# V0p2_Main_PCB2.net
KiCad netlist of a schematic drawn in EAGLE
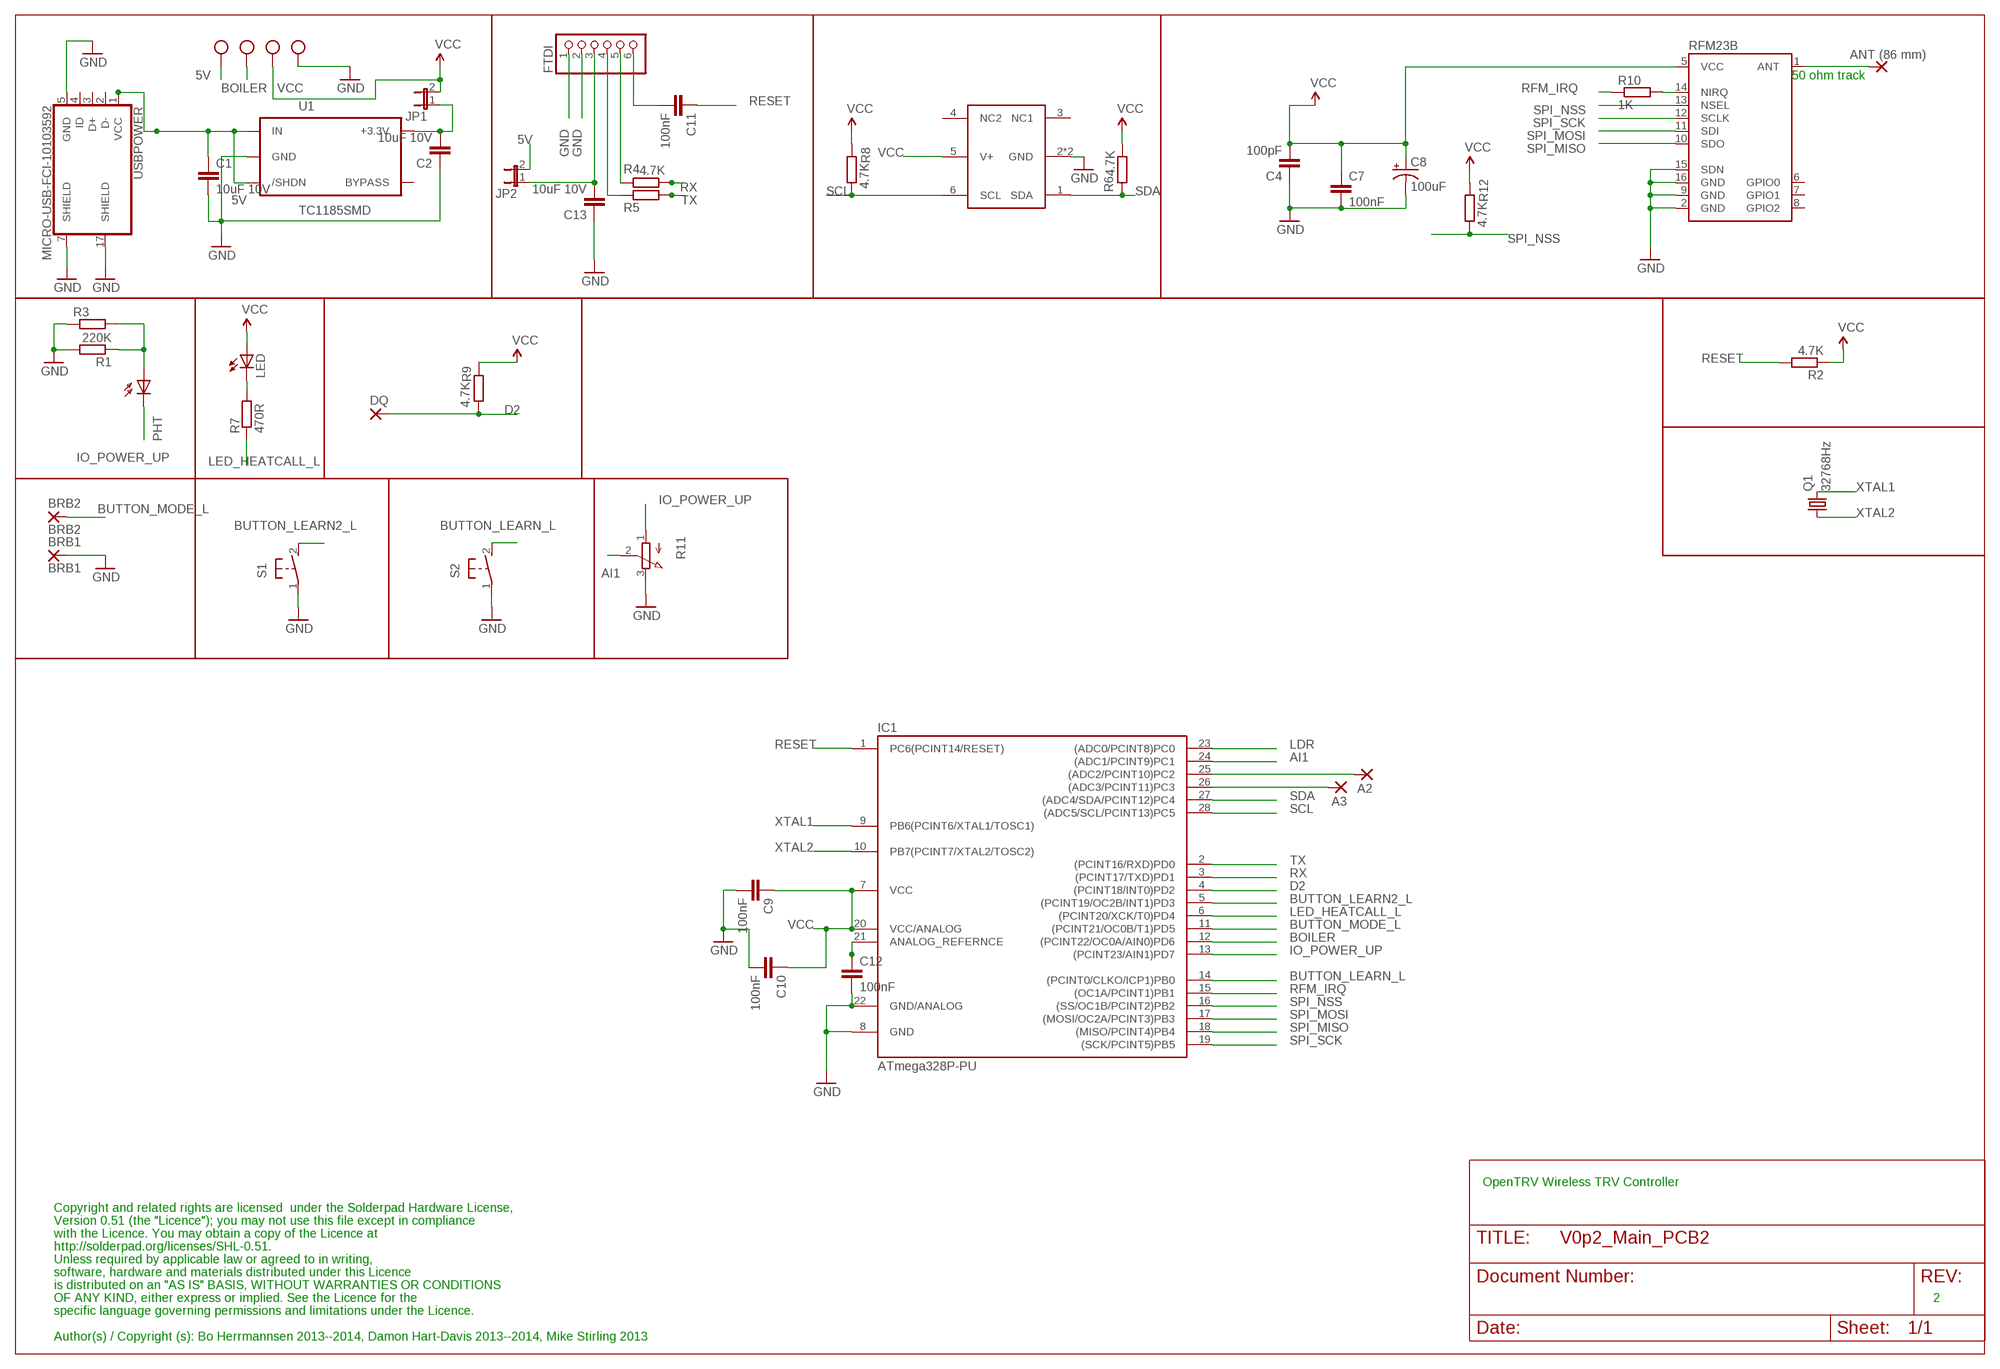
[diagram p0: schematic, sheet 1]

(export (version "E")
  (design (tool "Eeschema 10.0.6"))
  (components
    (comp (ref "A2")
      (value "2,15/1,0")
      (footprint "eagle-import:2,15_1,0")
      (libsource (lib "eagle-import") (part "2,15/1,0"))
    )
    (comp (ref "A3")
      (value "2,15/1,0")
      (footprint "eagle-import:2,15_1,0")
      (libsource (lib "eagle-import") (part "2,15/1,0"))
    )
    (comp (ref "ANT1")
      (value "ANT (86 mm)")
      (footprint "eagle-import:2,15_1,0")
      (libsource (lib "eagle-import") (part "2,15/1,0"))
    )
    (comp (ref "BRB1")
      (value "BRB1")
      (footprint "eagle-import:2,15_1,0")
      (libsource (lib "eagle-import") (part "2,15/1,0"))
    )
    (comp (ref "BRB2")
      (value "BRB2")
      (footprint "eagle-import:2,15_1,0")
      (libsource (lib "eagle-import") (part "2,15/1,0"))
    )
    (comp (ref "C1")
      (value "10uF 10V")
      (footprint "eagle-import:C0603")
      (libsource (lib "eagle-import") (part "C-EUC0603"))
    )
    (comp (ref "C2")
      (value "10uF 10V")
      (footprint "eagle-import:C0603")
      (libsource (lib "eagle-import") (part "C-EUC0603"))
    )
    (comp (ref "C4")
      (value "100pF")
      (footprint "eagle-import:C0603")
      (libsource (lib "eagle-import") (part "C-EUC0603"))
    )
    (comp (ref "C7")
      (value "100nF")
      (footprint "eagle-import:C0603")
      (libsource (lib "eagle-import") (part "C-EUC0603"))
    )
    (comp (ref "C8")
      (value "100uF")
      (footprint "eagle-import:EIA3216")
      (libsource (lib "eagle-import") (part "CAP_POL1206"))
    )
    (comp (ref "C9")
      (value "100nF")
      (footprint "eagle-import:C0603")
      (libsource (lib "eagle-import") (part "C-EUC0603"))
    )
    (comp (ref "C10")
      (value "100nF")
      (footprint "eagle-import:C0603")
      (libsource (lib "eagle-import") (part "C-EUC0603"))
    )
    (comp (ref "C11")
      (value "100nF")
      (footprint "eagle-import:C0603")
      (libsource (lib "eagle-import") (part "C-EUC0603"))
    )
    (comp (ref "C12")
      (value "100nF")
      (footprint "eagle-import:C0603")
      (libsource (lib "eagle-import") (part "C-EUC0603"))
    )
    (comp (ref "C13")
      (value "10uF 10V")
      (footprint "eagle-import:C0603")
      (libsource (lib "eagle-import") (part "C-EUC0603"))
    )
    (comp (ref "DQ")
      (value "2,15/1,0")
      (footprint "eagle-import:2,15_1,0")
      (libsource (lib "eagle-import") (part "2,15/1,0"))
    )
    (comp (ref "FTDI")
      (value "PINHD-1X6/90")
      (footprint "eagle-import:1X06_90")
      (libsource (lib "eagle-import") (part "PINHD-1X6/90"))
    )
    (comp (ref "IC1")
      (value "ATmega328P-PU")
      (footprint "eagle-import:DIL28-3")
      (libsource (lib "eagle-import") (part "ATMEGA168-PU"))
    )
    (comp (ref "JP1")
      (value "JP1E")
      (footprint "eagle-import:JP1")
      (libsource (lib "eagle-import") (part "JP1E"))
    )
    (comp (ref "JP2")
      (value "JP1E")
      (footprint "eagle-import:JP1")
      (libsource (lib "eagle-import") (part "JP1E"))
    )
    (comp (ref "LED")
      (value "LED3MM")
      (footprint "eagle-import:LED3MM")
      (libsource (lib "eagle-import") (part "LED3MM"))
    )
    (comp (ref "PHT")
      (value "BPX65")
      (footprint "eagle-import:BPX65")
      (fields (field (name "MPN") "BPX65."))
      (libsource (lib "eagle-import") (part "BPX65"))
    )
    (comp (ref "Q1")
      (value "32768Hz")
      (footprint "eagle-import:MC-306")
      (fields (field (name "MPN") "MC-306 60.0KHZ  100PPM ,12.5PF"))
      (libsource (lib "eagle-import") (part "MC-306"))
    )
    (comp (ref "R1")
      (value "220K")
      (footprint "eagle-import:R0603")
      (libsource (lib "eagle-import") (part "R-EU_R0603"))
    )
    (comp (ref "R2")
      (value "4.7K")
      (footprint "eagle-import:R0603")
      (libsource (lib "eagle-import") (part "R-EU_R0603"))
    )
    (comp (ref "R3")
      (value "R-EU_0309/V")
      (footprint "eagle-import:0309V")
      (libsource (lib "eagle-import") (part "R-EU_0309/V"))
    )
    (comp (ref "R4")
      (value "4.7K")
      (footprint "eagle-import:R0603")
      (libsource (lib "eagle-import") (part "R-EU_R0603"))
    )
    (comp (ref "R5")
      (value "4.7K")
      (footprint "eagle-import:R0603")
      (libsource (lib "eagle-import") (part "R-EU_R0603"))
    )
    (comp (ref "R6")
      (value "4.7K")
      (footprint "eagle-import:R0603")
      (libsource (lib "eagle-import") (part "R-EU_R0603"))
    )
    (comp (ref "R7")
      (value "470R")
      (footprint "eagle-import:R0603")
      (libsource (lib "eagle-import") (part "R-EU_R0603"))
    )
    (comp (ref "R8")
      (value "4.7K")
      (footprint "eagle-import:R0603")
      (libsource (lib "eagle-import") (part "R-EU_R0603"))
    )
    (comp (ref "R9")
      (value "4.7K")
      (footprint "eagle-import:R0603")
      (libsource (lib "eagle-import") (part "R-EU_R0603"))
    )
    (comp (ref "R10")
      (value "1K")
      (footprint "eagle-import:R0603")
      (libsource (lib "eagle-import") (part "R-EU_R0603"))
    )
    (comp (ref "R11")
      (value "EVUE2A")
      (footprint "eagle-import:EVUE")
      (libsource (lib "eagle-import") (part "EVUE2A"))
    )
    (comp (ref "R12")
      (value "4.7K")
      (footprint "eagle-import:R0603")
      (libsource (lib "eagle-import") (part "R-EU_R0603"))
    )
    (comp (ref "RFM23B")
      (value "RFM23B")
      (footprint "eagle-import:RFM23-XXX-S1")
      (libsource (lib "eagle-import") (part "RFM23B"))
    )
    (comp (ref "S1")
      (value "31-XX")
      (footprint "eagle-import:B3F-31XX")
      (libsource (lib "eagle-import") (part "31-XX"))
    )
    (comp (ref "S2")
      (value "31-XX")
      (footprint "eagle-import:B3F-31XX")
      (libsource (lib "eagle-import") (part "31-XX"))
    )
    (comp (ref "U$4")
      (value "SHT21")
      (footprint "eagle-import:SHT21")
      (libsource (lib "eagle-import") (part "SHT21"))
    )
    (comp (ref "U1")
      (value "TC1185SMD")
      (footprint "eagle-import:TC1185")
      (libsource (lib "eagle-import") (part "TC1185SMD"))
    )
    (comp (ref "USBPOWER")
      (value "MICRO-USB-FCI-10103592")
      (footprint "eagle-import:MICRO-USB-FCI-10103592")
      (libsource (lib "eagle-import") (part "MICRO-USB-FCI-10103592"))
    )
    (comp (ref "X1")
      (value "W237-102")
      (footprint "eagle-import:SCREWTERMINAL")
      (fields (field (name "MPN") "237-102"))
      (libsource (lib "eagle-import") (part "W237-102"))
    )
    (comp (ref "X2")
      (value "W237-102")
      (footprint "eagle-import:SCREWTERMINAL")
      (fields (field (name "MPN") "237-102"))
      (libsource (lib "eagle-import") (part "W237-102"))
    )
  )
  (nets
    (net (code "1") (name "/5V") (class "Default")
      (node (ref "C1") (pin "1") (pinfunction "1_1") (pintype "passive"))
      (node (ref "JP2") (pin "2") (pinfunction "2_2") (pintype "passive"))
      (node (ref "U1") (pin "1") (pinfunction "IN_1") (pintype "passive"))
      (node (ref "U1") (pin "3") (pinfunction "/SHDN_3") (pintype "passive"))
      (node (ref "USBPOWER") (pin "1") (pinfunction "VCC_1") (pintype "bidirectional"))
      (node (ref "X1") (pin "2") (pinfunction "KL_2") (pintype "passive"))
    )
    (net (code "2") (name "/AI1") (class "Default")
      (node (ref "IC1") (pin "24") (pinfunction "(ADC1/PCINT9)PC1_24") (pintype "bidirectional"))
      (node (ref "R11") (pin "2") (pinfunction "S_2") (pintype "passive"))
    )
    (net (code "3") (name "/BOILER") (class "Default")
      (node (ref "IC1") (pin "12") (pinfunction "(PCINT22/OC0A/AIN0)PD6_12") (pintype "bidirectional"))
      (node (ref "X1") (pin "1") (pinfunction "KL_1") (pintype "passive"))
    )
    (net (code "4") (name "/BUTTON_LEARN2_L") (class "Default")
      (node (ref "IC1") (pin "5") (pinfunction "(PCINT19/OC2B/INT1)PD3_5") (pintype "bidirectional"))
      (node (ref "S1") (pin "2") (pinfunction "S_2") (pintype "passive"))
    )
    (net (code "5") (name "/BUTTON_LEARN_L") (class "Default")
      (node (ref "IC1") (pin "14") (pinfunction "(PCINT0/CLKO/ICP1)PB0_14") (pintype "bidirectional"))
      (node (ref "S2") (pin "2") (pinfunction "S_2") (pintype "passive"))
    )
    (net (code "6") (name "/BUTTON_MODE_L") (class "Default")
      (node (ref "BRB2") (pin "1") (pinfunction "P_1") (pintype "passive"))
      (node (ref "IC1") (pin "11") (pinfunction "(PCINT21/OC0B/T1)PD5_11") (pintype "bidirectional"))
    )
    (net (code "7") (name "/D2") (class "Default")
      (node (ref "DQ") (pin "1") (pinfunction "P_1") (pintype "passive"))
      (node (ref "IC1") (pin "4") (pinfunction "(PCINT18/INT0)PD2_4") (pintype "bidirectional"))
      (node (ref "R9") (pin "1") (pinfunction "1_1") (pintype "passive"))
    )
    (net (code "8") (name "/IO_POWER_UP") (class "Default")
      (node (ref "IC1") (pin "13") (pinfunction "(PCINT23/AIN1)PD7_13") (pintype "bidirectional"))
      (node (ref "PHT") (pin "K") (pinfunction "C_K") (pintype "passive"))
      (node (ref "R11") (pin "1") (pinfunction "A_1") (pintype "passive"))
    )
    (net (code "9") (name "/LDR") (class "Default")
      (node (ref "IC1") (pin "23") (pinfunction "(ADC0/PCINT8)PC0_23") (pintype "bidirectional"))
      (node (ref "PHT") (pin "A") (pinfunction "A_A") (pintype "passive"))
      (node (ref "R1") (pin "1") (pinfunction "1_1") (pintype "passive"))
      (node (ref "R3") (pin "2") (pinfunction "2_2") (pintype "passive"))
    )
    (net (code "10") (name "/LED_HEATCALL_L") (class "Default")
      (node (ref "IC1") (pin "6") (pinfunction "(PCINT20/XCK/T0)PD4_6") (pintype "bidirectional"))
      (node (ref "R7") (pin "1") (pinfunction "1_1") (pintype "passive"))
    )
    (net (code "11") (name "/RESET") (class "Default")
      (node (ref "C11") (pin "1") (pinfunction "1_1") (pintype "passive"))
      (node (ref "IC1") (pin "1") (pinfunction "PC6(PCINT14/RESET)_1") (pintype "bidirectional"))
      (node (ref "R2") (pin "2") (pinfunction "2_2") (pintype "passive"))
    )
    (net (code "12") (name "/RFM_IRQ") (class "Default")
      (node (ref "IC1") (pin "15") (pinfunction "(OC1A/PCINT1)PB1_15") (pintype "bidirectional"))
      (node (ref "R10") (pin "1") (pinfunction "1_1") (pintype "passive"))
    )
    (net (code "13") (name "/RX") (class "Default")
      (node (ref "IC1") (pin "3") (pinfunction "(PCINT17/TXD)PD1_3") (pintype "bidirectional"))
      (node (ref "R4") (pin "1") (pinfunction "1_1") (pintype "passive"))
    )
    (net (code "14") (name "/SCL") (class "Default")
      (node (ref "IC1") (pin "28") (pinfunction "(ADC5/SCL/PCINT13)PC5_28") (pintype "bidirectional"))
      (node (ref "R8") (pin "1") (pinfunction "1_1") (pintype "passive"))
      (node (ref "U$4") (pin "6") (pinfunction "SCL_6") (pintype "bidirectional"))
    )
    (net (code "15") (name "/SDA") (class "Default")
      (node (ref "IC1") (pin "27") (pinfunction "(ADC4/SDA/PCINT12)PC4_27") (pintype "bidirectional"))
      (node (ref "R6") (pin "2") (pinfunction "2_2") (pintype "passive"))
      (node (ref "U$4") (pin "1") (pinfunction "SDA_1") (pintype "bidirectional"))
    )
    (net (code "16") (name "/SPI_MISO") (class "Default")
      (node (ref "IC1") (pin "18") (pinfunction "(MISO/PCINT4)PB4_18") (pintype "bidirectional"))
      (node (ref "RFM23B") (pin "10") (pinfunction "SDO_10") (pintype "output"))
    )
    (net (code "17") (name "/SPI_MOSI") (class "Default")
      (node (ref "IC1") (pin "17") (pinfunction "(MOSI/OC2A/PCINT3)PB3_17") (pintype "bidirectional"))
      (node (ref "RFM23B") (pin "11") (pinfunction "SDI_11") (pintype "input"))
    )
    (net (code "18") (name "/SPI_NSS") (class "Default")
      (node (ref "IC1") (pin "16") (pinfunction "(SS/OC1B/PCINT2)PB2_16") (pintype "bidirectional"))
      (node (ref "R12") (pin "1") (pinfunction "1_1") (pintype "passive"))
      (node (ref "RFM23B") (pin "13") (pinfunction "NSEL_13") (pintype "input"))
    )
    (net (code "19") (name "/SPI_SCK") (class "Default")
      (node (ref "IC1") (pin "19") (pinfunction "(SCK/PCINT5)PB5_19") (pintype "bidirectional"))
      (node (ref "RFM23B") (pin "12") (pinfunction "SCLK_12") (pintype "input"))
    )
    (net (code "20") (name "/TX") (class "Default")
      (node (ref "IC1") (pin "2") (pinfunction "(PCINT16/RXD)PD0_2") (pintype "bidirectional"))
      (node (ref "R5") (pin "1") (pinfunction "1_1") (pintype "passive"))
    )
    (net (code "21") (name "/XTAL1") (class "Default")
      (node (ref "IC1") (pin "9") (pinfunction "PB6(PCINT6/XTAL1/TOSC1)_9") (pintype "bidirectional"))
      (node (ref "Q1") (pin "4") (pinfunction "2_4") (pintype "passive"))
    )
    (net (code "22") (name "/XTAL2") (class "Default")
      (node (ref "IC1") (pin "10") (pinfunction "PB7(PCINT7/XTAL2/TOSC2)_10") (pintype "bidirectional"))
      (node (ref "Q1") (pin "1") (pinfunction "1_1") (pintype "passive"))
    )
    (net (code "23") (name "GND") (class "Default")
      (node (ref "BRB1") (pin "1") (pinfunction "P_1") (pintype "passive"))
      (node (ref "C1") (pin "2") (pinfunction "2_2") (pintype "passive"))
      (node (ref "C10") (pin "2") (pinfunction "2_2") (pintype "passive"))
      (node (ref "C12") (pin "2") (pinfunction "2_2") (pintype "passive"))
      (node (ref "C13") (pin "1") (pinfunction "1_1") (pintype "passive"))
      (node (ref "C2") (pin "1") (pinfunction "1_1") (pintype "passive"))
      (node (ref "C4") (pin "1") (pinfunction "1_1") (pintype "passive"))
      (node (ref "C7") (pin "2") (pinfunction "2_2") (pintype "passive"))
      (node (ref "C8") (pin "C") (pinfunction "-_C") (pintype "passive"))
      (node (ref "C9") (pin "2") (pinfunction "2_2") (pintype "passive"))
      (node (ref "FTDI") (pin "1") (pinfunction "1_1") (pintype "passive"))
      (node (ref "FTDI") (pin "2") (pinfunction "2_2") (pintype "passive"))
      (node (ref "IC1") (pin "22") (pinfunction "GND/ANALOG_22") (pintype "power_in"))
      (node (ref "IC1") (pin "8") (pinfunction "GND_8") (pintype "power_in"))
      (node (ref "R1") (pin "2") (pinfunction "2_2") (pintype "passive"))
      (node (ref "R11") (pin "3") (pinfunction "E_3") (pintype "passive"))
      (node (ref "R3") (pin "1") (pinfunction "1_1") (pintype "passive"))
      (node (ref "RFM23B") (pin "15") (pinfunction "SDN_15") (pintype "input"))
      (node (ref "RFM23B") (pin "16") (pinfunction "GND_16") (pintype "power_in"))
      (node (ref "RFM23B") (pin "2") (pinfunction "GND_2") (pintype "power_in"))
      (node (ref "RFM23B") (pin "9") (pinfunction "GND_9") (pintype "power_in"))
      (node (ref "S1") (pin "1") (pinfunction "P_1") (pintype "passive"))
      (node (ref "S2") (pin "1") (pinfunction "P_1") (pintype "passive"))
      (node (ref "U$4") (pin "2") (pinfunction "GND_2") (pintype "bidirectional"))
      (node (ref "U$4") (pin "P$1") (pinfunction "GND_P$1") (pintype "bidirectional"))
      (node (ref "U1") (pin "2") (pinfunction "GND_2") (pintype "passive"))
      (node (ref "USBPOWER") (pin "17") (pinfunction "SHIELD_17") (pintype "bidirectional"))
      (node (ref "USBPOWER") (pin "5") (pinfunction "GND_5") (pintype "bidirectional"))
      (node (ref "USBPOWER") (pin "7") (pinfunction "SHIELD_7") (pintype "bidirectional"))
      (node (ref "X2") (pin "2") (pinfunction "KL_2") (pintype "passive"))
    )
    (net (code "24") (name "Net-(A2-P)") (class "Default")
      (node (ref "A2") (pin "1") (pinfunction "P_1") (pintype "passive"))
      (node (ref "IC1") (pin "25") (pinfunction "(ADC2/PCINT10)PC2_25") (pintype "bidirectional"))
    )
    (net (code "25") (name "Net-(A3-P)") (class "Default")
      (node (ref "A3") (pin "1") (pinfunction "P_1") (pintype "passive"))
      (node (ref "IC1") (pin "26") (pinfunction "(ADC3/PCINT11)PC3_26") (pintype "bidirectional"))
    )
    (net (code "26") (name "Net-(ANT1-P)") (class "Default")
      (node (ref "ANT1") (pin "1") (pinfunction "P_1") (pintype "passive"))
      (node (ref "RFM23B") (pin "1") (pinfunction "ANT_1") (pintype "bidirectional"))
    )
    (net (code "27") (name "Net-(C11-Pad2)") (class "Default")
      (node (ref "C11") (pin "2") (pinfunction "2_2") (pintype "passive"))
      (node (ref "FTDI") (pin "6") (pinfunction "6_6") (pintype "passive"))
    )
    (net (code "28") (name "Net-(C13-Pad2)") (class "Default")
      (node (ref "C13") (pin "2") (pinfunction "2_2") (pintype "passive"))
      (node (ref "FTDI") (pin "3") (pinfunction "3_3") (pintype "passive"))
      (node (ref "JP2") (pin "1") (pinfunction "1_1") (pintype "passive"))
    )
    (net (code "29") (name "Net-(FTDI-Pad4)") (class "Default")
      (node (ref "FTDI") (pin "4") (pinfunction "4_4") (pintype "passive"))
      (node (ref "R5") (pin "2") (pinfunction "2_2") (pintype "passive"))
    )
    (net (code "30") (name "Net-(FTDI-Pad5)") (class "Default")
      (node (ref "FTDI") (pin "5") (pinfunction "5_5") (pintype "passive"))
      (node (ref "R4") (pin "2") (pinfunction "2_2") (pintype "passive"))
    )
    (net (code "31") (name "Net-(IC1-ANALOG_REFERNCE)") (class "Default")
      (node (ref "C12") (pin "1") (pinfunction "1_1") (pintype "passive"))
      (node (ref "IC1") (pin "21") (pinfunction "ANALOG_REFERNCE_21") (pintype "passive"))
    )
    (net (code "32") (name "Net-(LED-C)") (class "Default")
      (node (ref "LED") (pin "K") (pinfunction "C_K") (pintype "passive"))
      (node (ref "R7") (pin "2") (pinfunction "2_2") (pintype "passive"))
    )
    (net (code "33") (name "Net-(RFM23B-NIRQ)") (class "Default")
      (node (ref "R10") (pin "2") (pinfunction "2_2") (pintype "passive"))
      (node (ref "RFM23B") (pin "14") (pinfunction "NIRQ_14") (pintype "output"))
    )
    (net (code "34") (name "Net-(U1-+3.3V)") (class "Default")
      (node (ref "C2") (pin "2") (pinfunction "2_2") (pintype "passive"))
      (node (ref "JP1") (pin "1") (pinfunction "1_1") (pintype "passive"))
      (node (ref "U1") (pin "5") (pinfunction "+3.3V_5") (pintype "power_in"))
    )
    (net (code "35") (name "VCC") (class "Default")
      (node (ref "C10") (pin "1") (pinfunction "1_1") (pintype "passive"))
      (node (ref "C4") (pin "2") (pinfunction "2_2") (pintype "passive"))
      (node (ref "C7") (pin "1") (pinfunction "1_1") (pintype "passive"))
      (node (ref "C8") (pin "A") (pinfunction "+_A") (pintype "passive"))
      (node (ref "C9") (pin "1") (pinfunction "1_1") (pintype "passive"))
      (node (ref "IC1") (pin "20") (pinfunction "VCC/ANALOG_20") (pintype "passive"))
      (node (ref "IC1") (pin "7") (pinfunction "VCC_7") (pintype "power_in"))
      (node (ref "JP1") (pin "2") (pinfunction "2_2") (pintype "passive"))
      (node (ref "LED") (pin "A") (pinfunction "A_A") (pintype "passive"))
      (node (ref "R12") (pin "2") (pinfunction "2_2") (pintype "passive"))
      (node (ref "R2") (pin "1") (pinfunction "1_1") (pintype "passive"))
      (node (ref "R6") (pin "1") (pinfunction "1_1") (pintype "passive"))
      (node (ref "R8") (pin "2") (pinfunction "2_2") (pintype "passive"))
      (node (ref "R9") (pin "2") (pinfunction "2_2") (pintype "passive"))
      (node (ref "RFM23B") (pin "5") (pinfunction "VCC_5") (pintype "bidirectional"))
      (node (ref "U$4") (pin "5") (pinfunction "V+_5") (pintype "bidirectional"))
      (node (ref "X2") (pin "1") (pinfunction "KL_1") (pintype "passive"))
    )
    (net (code "36") (name "unconnected-(RFM23B-GPIO0-Pad6)") (class "Default")
      (node (ref "RFM23B") (pin "6") (pinfunction "GPIO0_6") (pintype "bidirectional"))
    )
    (net (code "37") (name "unconnected-(RFM23B-GPIO1-Pad7)") (class "Default")
      (node (ref "RFM23B") (pin "7") (pinfunction "GPIO1_7") (pintype "bidirectional"))
    )
    (net (code "38") (name "unconnected-(RFM23B-GPIO2-Pad8)") (class "Default")
      (node (ref "RFM23B") (pin "8") (pinfunction "GPIO2_8") (pintype "bidirectional"))
    )
    (net (code "39") (name "unconnected-(U$4-NC1-Pad3)") (class "Default")
      (node (ref "U$4") (pin "3") (pinfunction "NC1_3") (pintype "bidirectional"))
    )
    (net (code "40") (name "unconnected-(U$4-NC2-Pad4)") (class "Default")
      (node (ref "U$4") (pin "4") (pinfunction "NC2_4") (pintype "bidirectional"))
    )
    (net (code "41") (name "unconnected-(U1-BYPASS-Pad4)") (class "Default")
      (node (ref "U1") (pin "4") (pinfunction "BYPASS_4") (pintype "passive"))
    )
    (net (code "42") (name "unconnected-(USBPOWER-D+-Pad3)") (class "Default")
      (node (ref "USBPOWER") (pin "3") (pinfunction "D+_3") (pintype "bidirectional"))
    )
    (net (code "43") (name "unconnected-(USBPOWER-D--Pad2)") (class "Default")
      (node (ref "USBPOWER") (pin "2") (pinfunction "D-_2") (pintype "bidirectional"))
    )
    (net (code "44") (name "unconnected-(USBPOWER-ID-Pad4)") (class "Default")
      (node (ref "USBPOWER") (pin "4") (pinfunction "ID_4") (pintype "bidirectional"))
    )
  )
)
